# MUX.net
KiCad netlist of a schematic drawn in Altium Designer
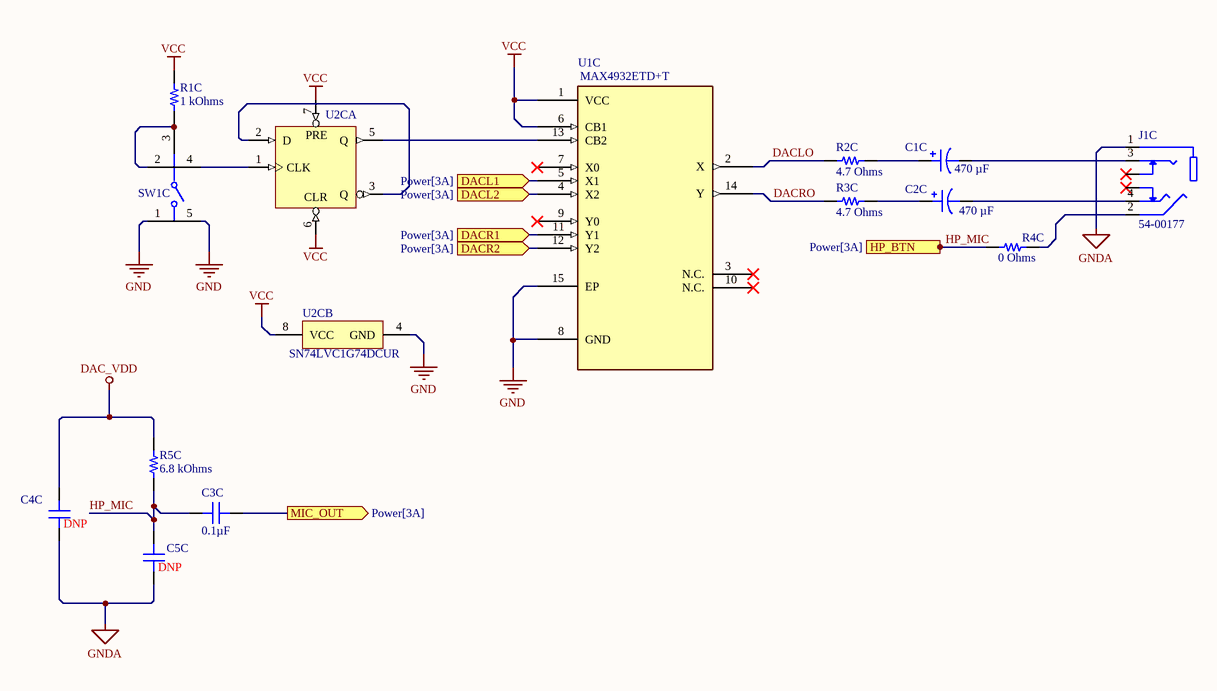
[diagram p0: MUX.SchDoc]

(export (version "E")
  (design (tool "Eeschema 10.0.6"))
  (components
    (comp (ref "C1C")
      (value "470 µF")
      (footprint "CAP ALSMD POLY 8.3MM H10.0MM")
      (description "POLYMER ALUMINUM SMT")
      (fields
        (field (name "PART NUMBER") "SVZ1AM471F9RE00RAXXX")
        (field (name "MANUFACTURER") "Aishi Capacitors (Hunan Aihua Group")
      )
      (libsource (lib "Postgres Altium Library - altium_library") (part "Polarised Capacitor"))
    )
    (comp (ref "C2C")
      (value "470 µF")
      (footprint "CAP ALSMD POLY 8.3MM H10.0MM")
      (description "POLYMER ALUMINUM SMT")
      (fields
        (field (name "PART NUMBER") "SVZ1AM471F9RE00RAXXX")
        (field (name "MANUFACTURER") "Aishi Capacitors (Hunan Aihua Group")
      )
      (libsource (lib "Postgres Altium Library - altium_library") (part "Polarised Capacitor"))
    )
    (comp (ref "C3C")
      (value "0.1µF")
      (footprint "CAP 0603_1608")
      (description "CAP CER 0.1UF 10V X7R 0603")
      (fields (field (name "PART NUMBER") "LD03ZC104KAB2A") (field (name "MANUFACTURER") "AVX Corporation"))
      (libsource (lib "Postgres Altium Library - altium_library") (part "Capacitor"))
    )
    (comp (ref "C4C")
      (value "DNP")
      (footprint "CAP 0603_1608")
      (description "CAP CER 0.1UF 10V X7R 0603")
      (fields (field (name "PART NUMBER") "LD03ZC104KAB2A") (field (name "MANUFACTURER") "AVX Corporation"))
      (libsource (lib "Postgres Altium Library - altium_library") (part "Capacitor"))
    )
    (comp (ref "C5C")
      (value "DNP")
      (footprint "CAP 0603_1608")
      (description "CAP CER 0.1UF 10V X7R 0603")
      (fields (field (name "PART NUMBER") "LD03ZC104KAB2A") (field (name "MANUFACTURER") "AVX Corporation"))
      (libsource (lib "Postgres Altium Library - altium_library") (part "Capacitor"))
    )
    (comp (ref "J1C")
      (value "54-00177")
      (footprint "TENSILITY_54-00177")
      (description "Connector, 4C audio jack, 3.5xL14 mm, SMT mount, gold plated")
      (fields (field (name "MF") "Tensility International Corp"))
      (libsource (lib "54-00177") (part "54-00177"))
    )
    (comp (ref "R1C")
      (value "1 kOhms")
      (footprint "RES 0603_1608")
      (description "CHIP RESISTOR THIN FLIM HIGH PRE")
      (fields (field (name "PART NUMBER") "RT0603FRE131KL") (field (name "TOLERANCE") "±1%"))
      (libsource (lib "Postgres Altium Library - altium_library") (part "Resistor"))
    )
    (comp (ref "R2C")
      (value "4.7 Ohms")
      (footprint "RES 0603_1608")
      (description "RES 4.7 OHM 1% 1/3W 0603")
      (fields (field (name "PART NUMBER") "SG73P1JTTD4R70F") (field (name "TOLERANCE") "±1%"))
      (libsource (lib "Postgres Altium Library - altium_library") (part "Resistor"))
    )
    (comp (ref "R3C")
      (value "4.7 Ohms")
      (footprint "RES 0603_1608")
      (description "RES 4.7 OHM 1% 1/3W 0603")
      (fields (field (name "PART NUMBER") "SG73P1JTTD4R70F") (field (name "TOLERANCE") "±1%"))
      (libsource (lib "Postgres Altium Library - altium_library") (part "Resistor"))
    )
    (comp (ref "R4C")
      (value "0 Ohms")
      (footprint "RES 0402_1005")
      (description "RES SMD 0 OHM JUMPER 1/16W 0402")
      (fields (field (name "PART NUMBER") "AC0402JR-070RL") (field (name "TOLERANCE") "Jumper"))
      (libsource (lib "Postgres Altium Library - altium_library") (part "Resistor"))
    )
    (comp (ref "R5C")
      (value "6.8 kOhms")
      (footprint "RES 0603_1608")
      (description "RES SMD 6.8K OHM 0.1% 1/10W 0603")
      (fields (field (name "PART NUMBER") "ERA-3AEB682V") (field (name "TOLERANCE") "±0.1%"))
      (libsource (lib "Postgres Altium Library - altium_library") (part "Resistor"))
    )
    (comp (ref "SW1C")
      (value "KMS231GPLFS")
      (footprint "FP-KMS231GPLFS-MFG")
      (description "SWITCH TACTILE SPST-NO 0.05A 50V")
      (libsource (lib "Altium Content Vault") (part "96206a584fada216e410b81990591b9"))
    )
    (comp (ref "U1C")
      (value "MAX4932ETD+T")
      (footprint "21-0137_T1433+2_MXM")
      (description "No Description Available")
      (libsource (lib "MAX4932ETD&plus_T") (part "MAX4932ETD+T"))
    )
    (comp (ref "U2C")
      (value "SN74LVC1G74DCUR")
      (footprint "DCU0008A_L")
      (description "Single Positive-Edge-Triggered D-Type Flip-Flop With Clear and Preset, DCU0008A, LARGE T&R")
      (fields
        (field (name "MANUFACTURER") "Texas Instruments")
        (field (name "GENERIC PART NUMBER") "SN74LVC1G74")
      )
      (libsource (lib "Altium Content Vault") (part "TI-SN74XXX1G74_2G74-8"))
    )
  )
  (nets
    (net (code "1") (name "/DACL1") (class "Default")
      (node (ref "U1C") (pin "5") (pinfunction "X1_5") (pintype "input"))
    )
    (net (code "2") (name "/DACL2") (class "Default")
      (node (ref "U1C") (pin "4") (pinfunction "X2_4") (pintype "input"))
    )
    (net (code "3") (name "/DACLO") (class "Default")
      (node (ref "R2C") (pin "1") (pinfunction "1_1") (pintype "passive"))
      (node (ref "U1C") (pin "2") (pinfunction "X_2") (pintype "output"))
    )
    (net (code "4") (name "/DACR1") (class "Default")
      (node (ref "U1C") (pin "11") (pinfunction "Y1_11") (pintype "input"))
    )
    (net (code "5") (name "/DACR2") (class "Default")
      (node (ref "U1C") (pin "12") (pinfunction "Y2_12") (pintype "input"))
    )
    (net (code "6") (name "/DACRO") (class "Default")
      (node (ref "R3C") (pin "1") (pinfunction "1_1") (pintype "passive"))
      (node (ref "U1C") (pin "14") (pinfunction "Y_14") (pintype "output"))
    )
    (net (code "7") (name "/HP_MIC") (class "Default")
      (node (ref "C3C") (pin "2") (pinfunction "2_2") (pintype "passive"))
      (node (ref "C5C") (pin "1") (pinfunction "1_1") (pintype "passive"))
      (node (ref "R4C") (pin "1") (pinfunction "1_1") (pintype "passive"))
      (node (ref "R5C") (pin "1") (pinfunction "1_1") (pintype "passive"))
    )
    (net (code "8") (name "/MIC_OUT") (class "Default")
      (node (ref "C3C") (pin "1") (pinfunction "1_1") (pintype "passive"))
    )
    (net (code "9") (name "DAC_VDD") (class "Default")
      (node (ref "C4C") (pin "1") (pinfunction "1_1") (pintype "passive"))
      (node (ref "R5C") (pin "2") (pinfunction "2_2") (pintype "passive"))
    )
    (net (code "10") (name "GND") (class "Default")
      (node (ref "SW1C") (pin "1") (pinfunction "1_1") (pintype "passive"))
      (node (ref "SW1C") (pin "5") (pinfunction "5_5") (pintype "passive"))
      (node (ref "U1C") (pin "15") (pinfunction "EP_15") (pintype "passive"))
      (node (ref "U1C") (pin "8") (pinfunction "GND_8") (pintype "power_in"))
      (node (ref "U2C") (pin "4") (pinfunction "GND_4") (pintype "power_in"))
    )
    (net (code "11") (name "GNDA") (class "Default")
      (node (ref "C4C") (pin "2") (pinfunction "2_2") (pintype "passive"))
      (node (ref "C5C") (pin "2") (pinfunction "2_2") (pintype "passive"))
      (node (ref "J1C") (pin "1") (pinfunction "1_1") (pintype "passive"))
    )
    (net (code "12") (name "Net-(C1C-Pad1)") (class "Default")
      (node (ref "C1C") (pin "1") (pinfunction "1_1") (pintype "passive"))
      (node (ref "R2C") (pin "2") (pinfunction "2_2") (pintype "passive"))
    )
    (net (code "13") (name "Net-(C1C-Pad2)") (class "Default")
      (node (ref "C1C") (pin "2") (pinfunction "2_2") (pintype "passive"))
      (node (ref "J1C") (pin "3") (pinfunction "3_3") (pintype "passive"))
    )
    (net (code "14") (name "Net-(C2C-Pad1)") (class "Default")
      (node (ref "C2C") (pin "1") (pinfunction "1_1") (pintype "passive"))
      (node (ref "R3C") (pin "2") (pinfunction "2_2") (pintype "passive"))
    )
    (net (code "15") (name "Net-(C2C-Pad2)") (class "Default")
      (node (ref "C2C") (pin "2") (pinfunction "2_2") (pintype "passive"))
      (node (ref "J1C") (pin "4") (pinfunction "4_4") (pintype "passive"))
    )
    (net (code "16") (name "Net-(J1C-Pad2)") (class "Default")
      (node (ref "J1C") (pin "2") (pinfunction "2_2") (pintype "passive"))
      (node (ref "R4C") (pin "2") (pinfunction "2_2") (pintype "passive"))
    )
    (net (code "17") (name "Net-(R1C-Pad1)") (class "Default")
      (node (ref "R1C") (pin "1") (pinfunction "1_1") (pintype "passive"))
      (node (ref "SW1C") (pin "2") (pinfunction "2_2") (pintype "passive"))
      (node (ref "SW1C") (pin "3") (pinfunction "3_3") (pintype "passive"))
    )
    (net (code "18") (name "Net-(U1C-CB2)") (class "Default")
      (node (ref "U1C") (pin "13") (pinfunction "CB2_13") (pintype "input"))
      (node (ref "U2C") (pin "5") (pinfunction "Q_5") (pintype "output"))
    )
    (net (code "19") (name "Net-(U2CA-CLK)") (class "Default")
      (node (ref "SW1C") (pin "4") (pinfunction "4_4") (pintype "passive"))
      (node (ref "U2C") (pin "1") (pinfunction "CLK_1") (pintype "input"))
    )
    (net (code "20") (name "Net-(U2CA-D)") (class "Default")
      (node (ref "U2C") (pin "2") (pinfunction "D_2") (pintype "input"))
      (node (ref "U2C") (pin "3") (pinfunction "Q_3") (pintype "output"))
    )
    (net (code "21") (name "VCC") (class "Default")
      (node (ref "R1C") (pin "2") (pinfunction "2_2") (pintype "passive"))
      (node (ref "U1C") (pin "1") (pinfunction "VCC_1") (pintype "power_in"))
      (node (ref "U1C") (pin "6") (pinfunction "CB1_6") (pintype "input"))
      (node (ref "U2C") (pin "6") (pinfunction "~{CLR}_6") (pintype "input"))
      (node (ref "U2C") (pin "7") (pinfunction "~{PRE}_7") (pintype "input"))
      (node (ref "U2C") (pin "8") (pinfunction "VCC_8") (pintype "power_in"))
    )
    (net (code "22") (name "unconnected-(J1C-Pad5)") (class "Default")
      (node (ref "J1C") (pin "5") (pinfunction "5_5") (pintype "passive+no_connect"))
    )
    (net (code "23") (name "unconnected-(J1C-Pad6)") (class "Default")
      (node (ref "J1C") (pin "6") (pinfunction "6_6") (pintype "passive+no_connect"))
    )
    (net (code "24") (name "unconnected-(U1C-N.C.-Pad3)") (class "Default")
      (node (ref "U1C") (pin "3") (pinfunction "N.C._3") (pintype "passive+no_connect"))
    )
    (net (code "25") (name "unconnected-(U1C-N.C.-Pad10)") (class "Default")
      (node (ref "U1C") (pin "10") (pinfunction "N.C._10") (pintype "passive+no_connect"))
    )
    (net (code "26") (name "unconnected-(U1C-X0-Pad7)") (class "Default")
      (node (ref "U1C") (pin "7") (pinfunction "X0_7") (pintype "input+no_connect"))
    )
    (net (code "27") (name "unconnected-(U1C-Y0-Pad9)") (class "Default")
      (node (ref "U1C") (pin "9") (pinfunction "Y0_9") (pintype "input+no_connect"))
    )
  )
)
